# 7segement4minidigits1badidea-mk-2.net
KiCad netlist of a schematic drawn in EAGLE
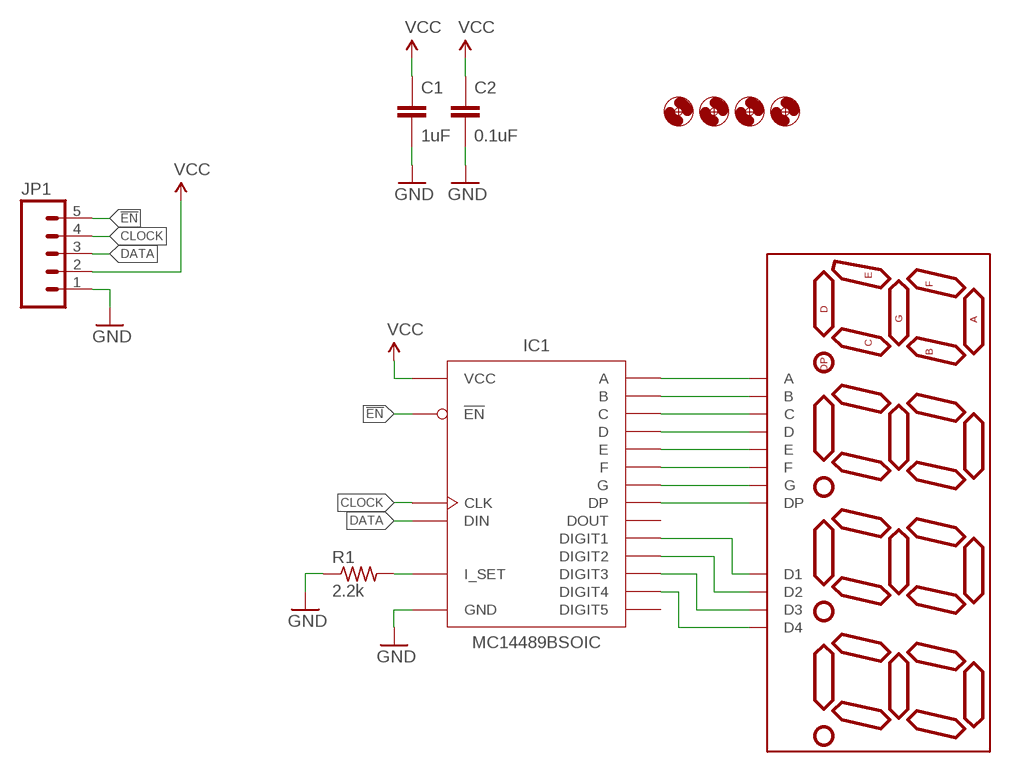
[diagram p0: schematic, sheet 1]

(export (version "E")
  (design (tool "Eeschema 10.0.6"))
  (components
    (comp (ref "BUBBLES!")
      (value "(>^_^)>")
      (footprint "eagle-import:DIP12-SMD-WAT")
      (libsource (lib "eagle-import") (part "7-SEGMENT-4DIGIT-COUNTERWAT"))
    )
    (comp (ref "C1")
      (value "1uF")
      (footprint "eagle-import:C0805")
      (libsource (lib "eagle-import") (part "CAPACITOR-CERAMICC0805"))
    )
    (comp (ref "C2")
      (value "0.1uF")
      (footprint "eagle-import:C0603")
      (libsource (lib "eagle-import") (part "CAPACITOR-CERAMICC0603"))
    )
    (comp (ref "H1")
      (value "HOLE#2")
      (footprint "eagle-import:HOLE-#2")
      (libsource (lib "eagle-import") (part "HOLE#2"))
    )
    (comp (ref "H2")
      (value "HOLE#2")
      (footprint "eagle-import:HOLE-#2")
      (libsource (lib "eagle-import") (part "HOLE#2"))
    )
    (comp (ref "H3")
      (value "HOLE#2")
      (footprint "eagle-import:HOLE-#2")
      (libsource (lib "eagle-import") (part "HOLE#2"))
    )
    (comp (ref "H4")
      (value "HOLE#2")
      (footprint "eagle-import:HOLE-#2")
      (libsource (lib "eagle-import") (part "HOLE#2"))
    )
    (comp (ref "IC1")
      (value "MC14489BSOIC")
      (footprint "eagle-import:SOP20W")
      (libsource (lib "eagle-import") (part "MC14489BSOIC"))
    )
    (comp (ref "JP1")
      (value "M05PTH")
      (footprint "eagle-import:1X05")
      (libsource (lib "eagle-import") (part "M05PTH"))
    )
    (comp (ref "R1")
      (value "2.2k")
      (footprint "eagle-import:R0603")
      (libsource (lib "eagle-import") (part "RESISTORR0603"))
    )
  )
  (nets
    (net (code "1") (name "/~{EN}") (class "Default")
      (node (ref "IC1") (pin "10") (pinfunction "~{EN}_10") (pintype "bidirectional"))
      (node (ref "JP1") (pin "5") (pinfunction "5_5") (pintype "passive"))
    )
    (net (code "2") (name "CLOCK") (class "Default")
      (node (ref "IC1") (pin "11") (pinfunction "CLK_11") (pintype "bidirectional"))
      (node (ref "JP1") (pin "4") (pinfunction "4_4") (pintype "passive"))
    )
    (net (code "3") (name "DATA") (class "Default")
      (node (ref "IC1") (pin "12") (pinfunction "DIN_12") (pintype "bidirectional"))
      (node (ref "JP1") (pin "3") (pinfunction "3_3") (pintype "passive"))
    )
    (net (code "4") (name "GND") (class "Default")
      (node (ref "C1") (pin "2") (pinfunction "2_2") (pintype "passive"))
      (node (ref "C2") (pin "2") (pinfunction "2_2") (pintype "passive"))
      (node (ref "IC1") (pin "14") (pinfunction "GND_14") (pintype "bidirectional"))
      (node (ref "JP1") (pin "1") (pinfunction "1_1") (pintype "passive"))
      (node (ref "R1") (pin "1") (pinfunction "1_1") (pintype "passive"))
    )
    (net (code "5") (name "Net-(BUBBLES!-A)") (class "Default")
      (node (ref "BUBBLES!") (pin "12") (pinfunction "A_12") (pintype "bidirectional"))
      (node (ref "IC1") (pin "7") (pinfunction "A_7") (pintype "bidirectional"))
    )
    (net (code "6") (name "Net-(BUBBLES!-B)") (class "Default")
      (node (ref "BUBBLES!") (pin "11") (pinfunction "B_11") (pintype "bidirectional"))
      (node (ref "IC1") (pin "6") (pinfunction "B_6") (pintype "bidirectional"))
    )
    (net (code "7") (name "Net-(BUBBLES!-C)") (class "Default")
      (node (ref "BUBBLES!") (pin "3") (pinfunction "C_3") (pintype "bidirectional"))
      (node (ref "IC1") (pin "5") (pinfunction "C_5") (pintype "bidirectional"))
    )
    (net (code "8") (name "Net-(BUBBLES!-D)") (class "Default")
      (node (ref "BUBBLES!") (pin "8") (pinfunction "D_8") (pintype "bidirectional"))
      (node (ref "IC1") (pin "4") (pinfunction "D_4") (pintype "bidirectional"))
    )
    (net (code "9") (name "Net-(BUBBLES!-D1)") (class "Default")
      (node (ref "BUBBLES!") (pin "1") (pinfunction "D1_1") (pintype "bidirectional"))
      (node (ref "IC1") (pin "9") (pinfunction "DIGIT1_9") (pintype "bidirectional"))
    )
    (net (code "10") (name "Net-(BUBBLES!-D2)") (class "Default")
      (node (ref "BUBBLES!") (pin "10") (pinfunction "D2_10") (pintype "bidirectional"))
      (node (ref "IC1") (pin "13") (pinfunction "DIGIT2_13") (pintype "bidirectional"))
    )
    (net (code "11") (name "Net-(BUBBLES!-D3)") (class "Default")
      (node (ref "BUBBLES!") (pin "4") (pinfunction "D3_4") (pintype "bidirectional"))
      (node (ref "IC1") (pin "15") (pinfunction "DIGIT3_15") (pintype "bidirectional"))
    )
    (net (code "12") (name "Net-(BUBBLES!-D4)") (class "Default")
      (node (ref "BUBBLES!") (pin "6") (pinfunction "D4_6") (pintype "bidirectional"))
      (node (ref "IC1") (pin "16") (pinfunction "DIGIT4_16") (pintype "bidirectional"))
    )
    (net (code "13") (name "Net-(BUBBLES!-DP)") (class "Default")
      (node (ref "BUBBLES!") (pin "5") (pinfunction "DP_5") (pintype "bidirectional"))
      (node (ref "IC1") (pin "19") (pinfunction "DP_19") (pintype "bidirectional"))
    )
    (net (code "14") (name "Net-(BUBBLES!-E)") (class "Default")
      (node (ref "BUBBLES!") (pin "2") (pinfunction "E_2") (pintype "bidirectional"))
      (node (ref "IC1") (pin "2") (pinfunction "E_2") (pintype "bidirectional"))
    )
    (net (code "15") (name "Net-(BUBBLES!-F)") (class "Default")
      (node (ref "BUBBLES!") (pin "9") (pinfunction "F_9") (pintype "bidirectional"))
      (node (ref "IC1") (pin "1") (pinfunction "F_1") (pintype "bidirectional"))
    )
    (net (code "16") (name "Net-(BUBBLES!-G)") (class "Default")
      (node (ref "BUBBLES!") (pin "7") (pinfunction "G_7") (pintype "bidirectional"))
      (node (ref "IC1") (pin "20") (pinfunction "G_20") (pintype "bidirectional"))
    )
    (net (code "17") (name "Net-(IC1-I_SET)") (class "Default")
      (node (ref "IC1") (pin "8") (pinfunction "I_SET_8") (pintype "bidirectional"))
      (node (ref "R1") (pin "2") (pinfunction "2_2") (pintype "passive"))
    )
    (net (code "18") (name "VCC") (class "Default")
      (node (ref "C1") (pin "1") (pinfunction "1_1") (pintype "passive"))
      (node (ref "C2") (pin "1") (pinfunction "1_1") (pintype "passive"))
      (node (ref "IC1") (pin "3") (pinfunction "VCC_3") (pintype "bidirectional"))
      (node (ref "JP1") (pin "2") (pinfunction "2_2") (pintype "passive"))
    )
    (net (code "19") (name "unconnected-(IC1-DIGIT5-Pad17)") (class "Default")
      (node (ref "IC1") (pin "17") (pinfunction "DIGIT5_17") (pintype "bidirectional"))
    )
    (net (code "20") (name "unconnected-(IC1-DOUT-Pad18)") (class "Default")
      (node (ref "IC1") (pin "18") (pinfunction "DOUT_18") (pintype "bidirectional"))
    )
  )
)
